# bob.net
KiCad netlist of a schematic drawn in Altium Designer
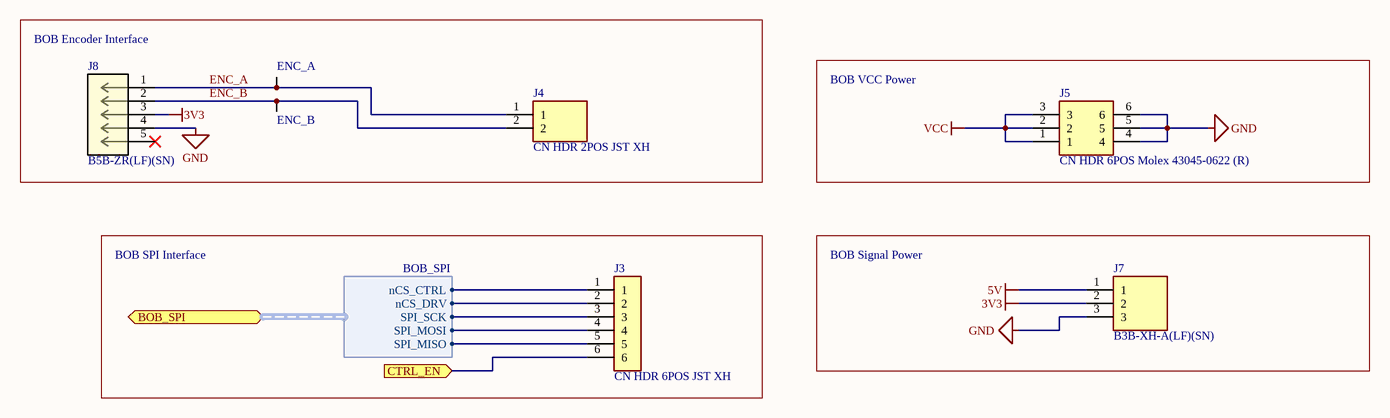
[diagram p0: bob.SchDoc]

(export (version "E")
  (design (tool "Eeschema 10.0.6"))
  (components
    (comp (ref "ENC_A")
      (value "Test Point (Via)")
      (footprint "TP")
      (libsource (lib "AltiumLibraries") (part "Test Point (Via)"))
    )
    (comp (ref "ENC_B")
      (value "Test Point (Via)")
      (footprint "TP")
      (libsource (lib "AltiumLibraries") (part "Test Point (Via)"))
    )
    (comp (ref "J3")
      (value "CN HDR 6POS JST XH")
      (footprint "JST_B6B-XH-A(LF)(SN)")
      (description "Connector Header Through Hole 6 position 0.098\" (2.50mm)")
      (fields (field (name "MP") "B6B-XH-A(LF)(SN)") (field (name "MF") "JST Sales"))
      (libsource (lib "AltiumLibraries") (part "CN HDR 6POS JST XH"))
    )
    (comp (ref "J4")
      (value "CN HDR 2POS JST XH")
      (footprint "JST_B2B-XH-A(LF)(SN)")
      (description "Connector Header Through Hole 2 position 0.098 _2.50mm_\r\nJST XH")
      (fields (field (name "MP") "B2B-XH-A_LF__SN_") (field (name "MF") "JST Sales"))
      (libsource (lib "AltiumLibraries") (part "CN HDR 2POS JST XH"))
    )
    (comp (ref "J5")
      (value "CN HDR 6POS Molex 43045-0622 (R)")
      (footprint "430450622")
      (description "Molex 43045-0622 6POS Microfit\r\ndual row, right angle")
      (libsource (lib "AltiumLibraries") (part "CN HDR 6POS Molex 43045-0622 (R)"))
    )
    (comp (ref "J7")
      (value "B3B-XH-A(LF)(SN)")
      (footprint "JST_B3B-XH-A(LF)(SN)")
      (description "CN 3POS TH JST XH")
      (fields (field (name "MF") "JST Sales"))
      (libsource (lib "AltiumLibraries") (part "CN 3POS TH JSTXH"))
    )
    (comp (ref "J8")
      (value "B5B-ZR(LF)(SN)")
      (footprint "JST_B5B-ZR(LF)(SN)")
      (description "Connector Header Through Hole 5 position 0.059 (1.50mm)")
      (fields (field (name "MF") "JST Sales"))
      (libsource (lib "AltiumLibraries") (part "CN 5POS JST ZR"))
    )
  )
  (nets
    (net (code "2") (name "/CTRL_EN") (class "Default")
      (node (ref "J3") (pin "6") (pinfunction "6_6") (pintype "passive"))
    )
    (net (code "3") (name "/ENC_A") (class "Default")
      (node (ref "ENC_A") (pin "1") (pinfunction "1_1") (pintype "passive"))
      (node (ref "J4") (pin "1") (pinfunction "1_1") (pintype "passive"))
      (node (ref "J8") (pin "1") (pinfunction "1_1") (pintype "passive"))
    )
    (net (code "4") (name "/ENC_B") (class "Default")
      (node (ref "ENC_B") (pin "1") (pinfunction "1_1") (pintype "passive"))
      (node (ref "J4") (pin "2") (pinfunction "2_2") (pintype "passive"))
      (node (ref "J8") (pin "2") (pinfunction "2_2") (pintype "passive"))
    )
    (net (code "5") (name "/SPI_MISO") (class "Default")
      (node (ref "J3") (pin "5") (pinfunction "5_5") (pintype "passive"))
    )
    (net (code "6") (name "/SPI_MOSI") (class "Default")
      (node (ref "J3") (pin "4") (pinfunction "4_4") (pintype "passive"))
    )
    (net (code "7") (name "/SPI_SCK") (class "Default")
      (node (ref "J3") (pin "3") (pinfunction "3_3") (pintype "passive"))
    )
    (net (code "8") (name "/nCS_CTRL") (class "Default")
      (node (ref "J3") (pin "1") (pinfunction "1_1") (pintype "passive"))
    )
    (net (code "9") (name "/nCS_DRV") (class "Default")
      (node (ref "J3") (pin "2") (pinfunction "2_2") (pintype "passive"))
    )
    (net (code "11") (name "3V3") (class "Default")
      (node (ref "J7") (pin "2") (pinfunction "2_2") (pintype "passive"))
      (node (ref "J8") (pin "3") (pinfunction "3_3") (pintype "passive"))
    )
    (net (code "12") (name "5V") (class "Default")
      (node (ref "J7") (pin "1") (pinfunction "1_1") (pintype "passive"))
    )
    (net (code "13") (name "GND") (class "Default")
      (node (ref "J5") (pin "4") (pinfunction "4_4") (pintype "passive"))
      (node (ref "J5") (pin "5") (pinfunction "5_5") (pintype "passive"))
      (node (ref "J5") (pin "6") (pinfunction "6_6") (pintype "passive"))
      (node (ref "J7") (pin "3") (pinfunction "3_3") (pintype "passive"))
      (node (ref "J8") (pin "4") (pinfunction "4_4") (pintype "passive"))
    )
    (net (code "14") (name "VCC") (class "Default")
      (node (ref "J5") (pin "1") (pinfunction "1_1") (pintype "passive"))
      (node (ref "J5") (pin "2") (pinfunction "2_2") (pintype "passive"))
      (node (ref "J5") (pin "3") (pinfunction "3_3") (pintype "passive"))
    )
    (net (code "15") (name "unconnected-(J8-Pad5)") (class "Default")
      (node (ref "J8") (pin "5") (pinfunction "5_5") (pintype "passive+no_connect"))
    )
  )
)
